# 2_Shutdown.net
KiCad netlist of a schematic drawn in Altium Designer
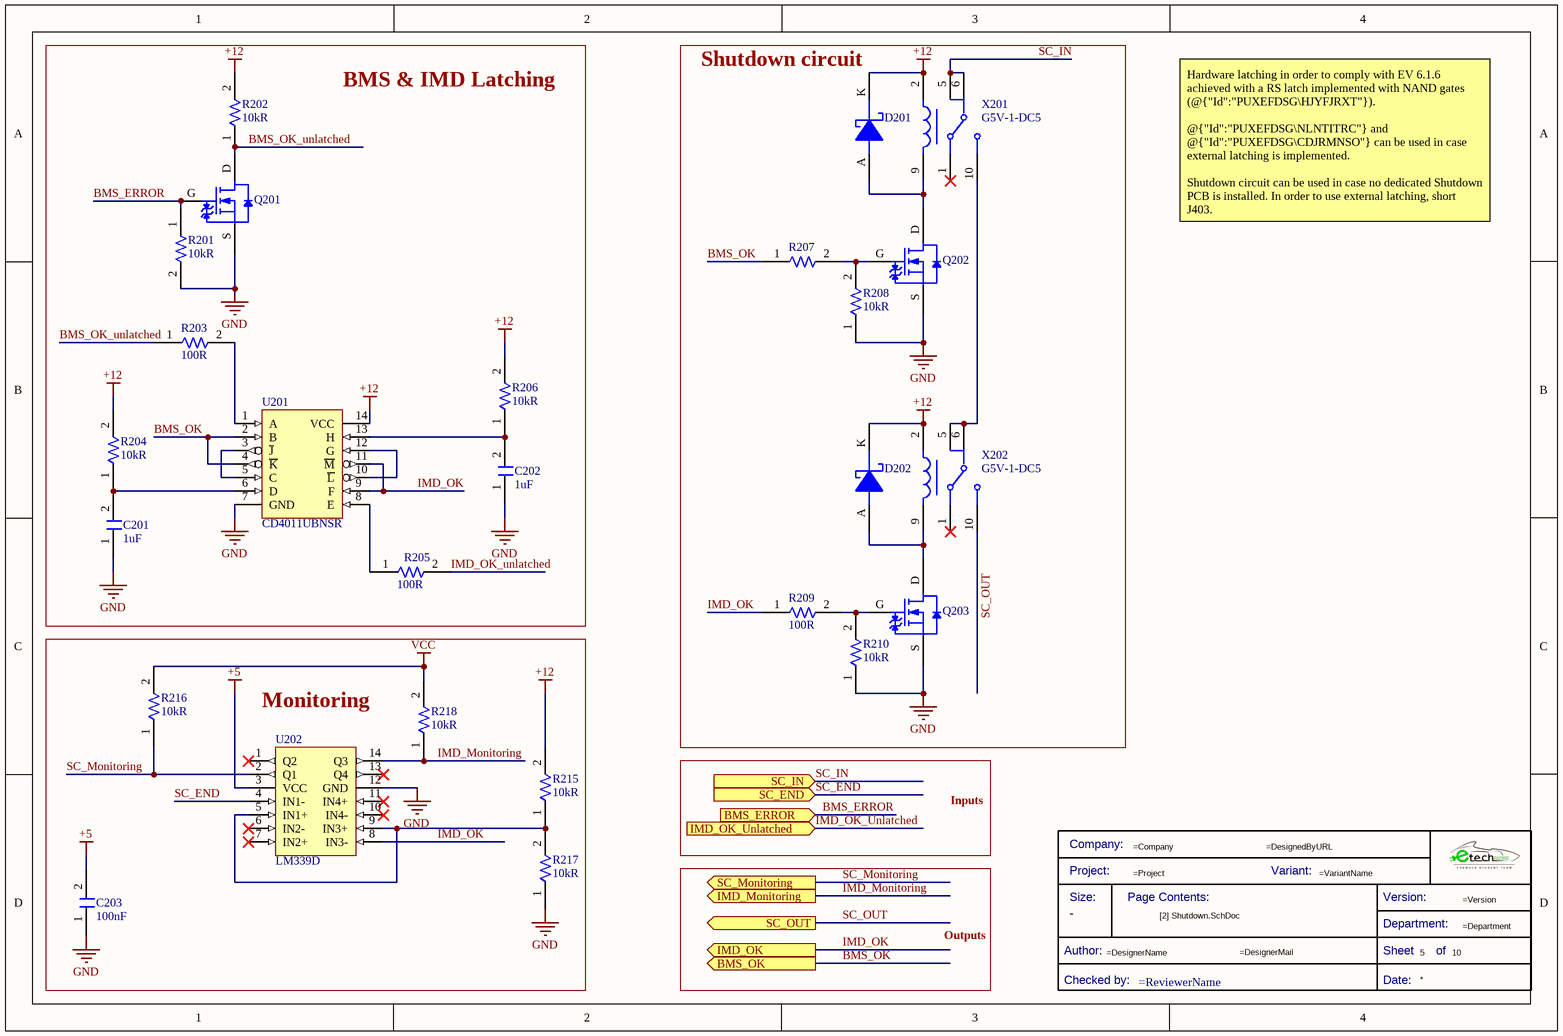
[diagram p0: [2] Shutdown.SchDoc]

(export (version "E")
  (design (tool "Eeschema 10.0.6"))
  (components
    (comp (ref "*")
      (value "Title Block_template")
      (description "Standard Title Block")
      (fields (field (name "SIZE") "-"))
      (libsource (lib "e-Tech_Racing") (part "Title Block_template"))
    )
    (comp (ref "C201")
      (value "885012207103")
      (footprint "C0805FNPC-R")
      (fields
        (field (name "TOLERANCE") "10%")
        (field (name "CAPACITANCE") "1uF")
        (field (name ".CREATOR") "GP")
      )
      (libsource (lib "Passives") (part "C1u-50V-0805FNPC-X7R"))
    )
    (comp (ref "C202")
      (value "885012207103")
      (footprint "C0805FNPC-R")
      (fields
        (field (name "TOLERANCE") "10%")
        (field (name "CAPACITANCE") "1uF")
        (field (name ".CREATOR") "GP")
      )
      (libsource (lib "Passives") (part "C1u-50V-0805FNPC-X7R"))
    )
    (comp (ref "C203")
      (value "885012207098")
      (footprint "C0805FNPC-R")
      (description "Cap, 0.1ΜF, 50V, 10%, X7R, 0805")
      (fields
        (field (name "TOLERANCE") "10%")
        (field (name "CAPACITANCE") "100nF")
        (field (name ".CREATOR") "DR")
      )
      (libsource (lib "Passives") (part "C100n-50V-0805FNPC-X7R"))
    )
    (comp (ref "D201")
      (value "MBR0530")
      (footprint "DSC-SOD123")
      (description "VR=30V IF=500mA 30pF P=410mW")
      (fields (field (name ".CREATOR") "GP"))
      (libsource (lib "Filter components") (part "DSC-0.5/30-SOD123"))
    )
    (comp (ref "D202")
      (value "MBR0530")
      (footprint "DSC-SOD123")
      (description "VR=30V IF=500mA 30pF P=410mW")
      (fields (field (name ".CREATOR") "GP"))
      (libsource (lib "Filter components") (part "DSC-0.5/30-SOD123"))
    )
    (comp (ref "Q201")
      (value "CPH3455-TL-H")
      (footprint "TRT-NCH-3/35-CPH")
      (description "CPH3455-TL-H N-channel MOSFET Transistor; 3 A; 35 V; 3-Pin CPH")
      (fields (field (name "MANUFACTURER") "ON Semiconductor") (field (name ".CREATOR") "GP"))
      (libsource (lib "Semiconductor") (part "TRT-NCH-3/35-CPH"))
    )
    (comp (ref "Q202")
      (value "CPH3455-TL-H")
      (footprint "TRT-NCH-3/35-CPH")
      (description "CPH3455-TL-H N-channel MOSFET Transistor; 3 A; 35 V; 3-Pin CPH")
      (fields (field (name "MANUFACTURER") "ON Semiconductor") (field (name ".CREATOR") "GP"))
      (libsource (lib "Semiconductor") (part "TRT-NCH-3/35-CPH"))
    )
    (comp (ref "Q203")
      (value "CPH3455-TL-H")
      (footprint "TRT-NCH-3/35-CPH")
      (description "CPH3455-TL-H N-channel MOSFET Transistor; 3 A; 35 V; 3-Pin CPH")
      (fields (field (name "MANUFACTURER") "ON Semiconductor") (field (name ".CREATOR") "GP"))
      (libsource (lib "Semiconductor") (part "TRT-NCH-3/35-CPH"))
    )
    (comp (ref "R201")
      (value "CR0805-JW-103ELF")
      (footprint "R0805FTK")
      (fields
        (field (name "TOLERANCE") "5%")
        (field (name "RESISTANCE") "10kR")
        (field (name ".CREATOR") "DR")
      )
      (libsource (lib "Passives") (part "R10k-0805FTK"))
    )
    (comp (ref "R202")
      (value "CR0805-JW-103ELF")
      (footprint "R0805FTK")
      (fields
        (field (name "TOLERANCE") "5%")
        (field (name "RESISTANCE") "10kR")
        (field (name ".CREATOR") "DR")
      )
      (libsource (lib "Passives") (part "R10k-0805FTK"))
    )
    (comp (ref "R203")
      (value "CR0805-FX-1000ELF")
      (footprint "R0805FTK")
      (description "Res Thick Film 0805 100 Ohm 1% 1/8W ±100ppm/°C Molded SMD SMD Paper Tape on Plastic Reel")
      (fields
        (field (name "TOLERANCE") "1%")
        (field (name "RESISTANCE") "100R")
        (field (name ".CREATOR") "DR")
      )
      (libsource (lib "Passives") (part "R100-0805FTK"))
    )
    (comp (ref "R204")
      (value "CR0805-JW-103ELF")
      (footprint "R0805FTK")
      (fields
        (field (name "TOLERANCE") "5%")
        (field (name "RESISTANCE") "10kR")
        (field (name ".CREATOR") "DR")
      )
      (libsource (lib "Passives") (part "R10k-0805FTK"))
    )
    (comp (ref "R205")
      (value "CR0805-FX-1000ELF")
      (footprint "R0805FTK")
      (description "Res Thick Film 0805 100 Ohm 1% 1/8W ±100ppm/°C Molded SMD SMD Paper Tape on Plastic Reel")
      (fields
        (field (name "TOLERANCE") "1%")
        (field (name "RESISTANCE") "100R")
        (field (name ".CREATOR") "DR")
      )
      (libsource (lib "Passives") (part "R100-0805FTK"))
    )
    (comp (ref "R206")
      (value "CR0805-JW-103ELF")
      (footprint "R0805FTK")
      (fields
        (field (name "TOLERANCE") "5%")
        (field (name "RESISTANCE") "10kR")
        (field (name ".CREATOR") "DR")
      )
      (libsource (lib "Passives") (part "R10k-0805FTK"))
    )
    (comp (ref "R207")
      (value "CR0805-FX-1000ELF")
      (footprint "R0805FTK")
      (description "Res Thick Film 0805 100 Ohm 1% 1/8W ±100ppm/°C Molded SMD SMD Paper Tape on Plastic Reel")
      (fields (field (name "TOLERANCE") "1%") (field (name ".CREATOR") "DR"))
      (libsource (lib "Passives") (part "R100-0805FTK"))
    )
    (comp (ref "R208")
      (value "CR0805-JW-103ELF")
      (footprint "R0805FTK")
      (fields
        (field (name "TOLERANCE") "5%")
        (field (name "RESISTANCE") "10kR")
        (field (name ".CREATOR") "DR")
      )
      (libsource (lib "Passives") (part "R10k-0805FTK"))
    )
    (comp (ref "R209")
      (value "CR0805-FX-1000ELF")
      (footprint "R0805FTK")
      (description "Res Thick Film 0805 100 Ohm 1% 1/8W ±100ppm/°C Molded SMD SMD Paper Tape on Plastic Reel")
      (fields
        (field (name "TOLERANCE") "1%")
        (field (name "RESISTANCE") "100R")
        (field (name ".CREATOR") "DR")
      )
      (libsource (lib "Passives") (part "R100-0805FTK"))
    )
    (comp (ref "R210")
      (value "CR0805-JW-103ELF")
      (footprint "R0805FTK")
      (fields
        (field (name "TOLERANCE") "5%")
        (field (name "RESISTANCE") "10kR")
        (field (name ".CREATOR") "DR")
      )
      (libsource (lib "Passives") (part "R10k-0805FTK"))
    )
    (comp (ref "R215")
      (value "CR0805-JW-103ELF")
      (footprint "R0805FTK")
      (fields
        (field (name "TOLERANCE") "5%")
        (field (name "RESISTANCE") "10kR")
        (field (name ".CREATOR") "DR")
      )
      (libsource (lib "Passives") (part "R10k-0805FTK"))
    )
    (comp (ref "R216")
      (value "CR0805-JW-103ELF")
      (footprint "R0805FTK")
      (fields
        (field (name "TOLERANCE") "5%")
        (field (name "RESISTANCE") "10kR")
        (field (name ".CREATOR") "DR")
      )
      (libsource (lib "Passives") (part "R10k-0805FTK"))
    )
    (comp (ref "R217")
      (value "CR0805-JW-103ELF")
      (footprint "R0805FTK")
      (fields
        (field (name "TOLERANCE") "5%")
        (field (name "RESISTANCE") "10kR")
        (field (name ".CREATOR") "DR")
      )
      (libsource (lib "Passives") (part "R10k-0805FTK"))
    )
    (comp (ref "R218")
      (value "CR0805-JW-103ELF")
      (footprint "R0805FTK")
      (fields
        (field (name "TOLERANCE") "5%")
        (field (name "RESISTANCE") "10kR")
        (field (name ".CREATOR") "DR")
      )
      (libsource (lib "Passives") (part "R10k-0805FTK"))
    )
    (comp (ref "U201")
      (value "CD4011UBSNR")
      (footprint "ARRAY_4_NAND")
      (description "CD4011UB Cmos Quad 2-INPUT Nand")
      (fields
        (field (name "MANUFACTURER") "Texas Instruments")
        (field (name "MANUFACTURER PART NUMBER") "CD4011UBNSR")
        (field (name ".CREATOR") "DO")
      )
      (libsource (lib "Integrated circuits") (part "Array_4_NAND"))
    )
    (comp (ref "U202")
      (value "LM339D")
      (footprint "Array_4_Amp_LM339D")
      (description "Comparator Quad ±18V/36V 14-Pin SOIC Tube")
      (fields
        (field (name "MANUFACTURER") "Texas Instruments")
        (field (name "MANUFACTURER PART NUMBER") "LM339D")
        (field (name ".CREATOR") "DO")
      )
      (libsource (lib "Integrated circuits") (part "Array_4_Amp_LM339D"))
    )
    (comp (ref "X201")
      (value "G5V-1-DC5")
      (footprint "Relay_G5V-1-DC5")
      (description "Electromechanical Relay SPDT 1A 5VDC 167Ohm Through Hole")
      (fields
        (field (name "MANUFACTURER") "Omron")
        (field (name "SUPPLIER PART NUMBER 1") "G5V-1-DC5")
        (field (name ".CREATOR") "DO")
      )
      (libsource (lib "Electromechanical") (part "Relay_G5V-1-DC5"))
    )
    (comp (ref "X202")
      (value "G5V-1-DC5")
      (footprint "Relay_G5V-1-DC5")
      (description "Electromechanical Relay SPDT 1A 5VDC 167Ohm Through Hole")
      (fields
        (field (name "MANUFACTURER") "Omron")
        (field (name "SUPPLIER PART NUMBER 1") "G5V-1-DC5")
        (field (name ".CREATOR") "DO")
      )
      (libsource (lib "Electromechanical") (part "Relay_G5V-1-DC5"))
    )
  )
  (nets
    (net (code "1") (name "+5") (class "Default")
      (node (ref "C203") (pin "2") (pinfunction "2_2") (pintype "passive"))
      (node (ref "U202") (pin "3") (pinfunction "VCC_3") (pintype "power_in"))
    )
    (net (code "2") (name "+12") (class "Default")
      (node (ref "D201") (pin "K") (pinfunction "K_K") (pintype "passive"))
      (node (ref "D202") (pin "K") (pinfunction "K_K") (pintype "passive"))
      (node (ref "R202") (pin "2") (pinfunction "2_2") (pintype "passive"))
      (node (ref "R204") (pin "2") (pinfunction "2_2") (pintype "passive"))
      (node (ref "R206") (pin "2") (pinfunction "2_2") (pintype "passive"))
      (node (ref "R215") (pin "2") (pinfunction "2_2") (pintype "passive"))
      (node (ref "U201") (pin "14") (pinfunction "VCC_14") (pintype "power_in"))
      (node (ref "X201") (pin "2") (pinfunction "2_2") (pintype "passive"))
      (node (ref "X202") (pin "2") (pinfunction "2_2") (pintype "passive"))
    )
    (net (code "3") (name "/BMS_ERROR") (class "Default")
      (node (ref "Q201") (pin "G") (pinfunction "G_G") (pintype "passive"))
      (node (ref "R201") (pin "1") (pinfunction "1_1") (pintype "passive"))
    )
    (net (code "4") (name "/BMS_OK") (class "Default")
      (node (ref "R207") (pin "1") (pinfunction "1_1") (pintype "passive"))
      (node (ref "U201") (pin "2") (pinfunction "B_2") (pintype "input"))
      (node (ref "U201") (pin "4") (pinfunction "~{K}_4") (pintype "output"))
    )
    (net (code "5") (name "/BMS_OK_unlatched") (class "Default")
      (node (ref "Q201") (pin "D") (pinfunction "D_D") (pintype "passive"))
      (node (ref "R202") (pin "1") (pinfunction "1_1") (pintype "passive"))
      (node (ref "R203") (pin "1") (pinfunction "1_1") (pintype "passive"))
    )
    (net (code "6") (name "/IMD_Monitoring") (class "Default")
      (node (ref "R218") (pin "1") (pinfunction "1_1") (pintype "passive"))
      (node (ref "U202") (pin "14") (pinfunction "Q3_14") (pintype "output"))
    )
    (net (code "7") (name "/IMD_OK") (class "Default")
      (node (ref "R209") (pin "1") (pinfunction "1_1") (pintype "passive"))
      (node (ref "U201") (pin "11") (pinfunction "~{M}_11") (pintype "output"))
      (node (ref "U201") (pin "9") (pinfunction "F_9") (pintype "input"))
      (node (ref "U202") (pin "8") (pinfunction "IN3-_8") (pintype "input"))
    )
    (net (code "9") (name "/IMD_OK_unlatched") (class "Default")
      (node (ref "R205") (pin "2") (pinfunction "2_2") (pintype "passive"))
    )
    (net (code "10") (name "/SC_END") (class "Default")
      (node (ref "U202") (pin "4") (pinfunction "IN1-_4") (pintype "input"))
    )
    (net (code "11") (name "/SC_IN") (class "Default")
      (node (ref "X201") (pin "5") (pinfunction "5_5") (pintype "passive"))
      (node (ref "X201") (pin "6") (pinfunction "6_6") (pintype "passive"))
    )
    (net (code "12") (name "/SC_Monitoring") (class "Default")
      (node (ref "R216") (pin "1") (pinfunction "1_1") (pintype "passive"))
      (node (ref "U202") (pin "2") (pinfunction "Q1_2") (pintype "output"))
    )
    (net (code "13") (name "/SC_OUT") (class "Default")
      (node (ref "X202") (pin "10") (pinfunction "10_10") (pintype "passive"))
    )
    (net (code "14") (name "GND") (class "Default")
      (node (ref "C201") (pin "1") (pinfunction "1_1") (pintype "passive"))
      (node (ref "C202") (pin "1") (pinfunction "1_1") (pintype "passive"))
      (node (ref "C203") (pin "1") (pinfunction "1_1") (pintype "passive"))
      (node (ref "Q201") (pin "S") (pinfunction "S_S") (pintype "passive"))
      (node (ref "Q202") (pin "S") (pinfunction "S_S") (pintype "passive"))
      (node (ref "Q203") (pin "S") (pinfunction "S_S") (pintype "passive"))
      (node (ref "R201") (pin "2") (pinfunction "2_2") (pintype "passive"))
      (node (ref "R208") (pin "1") (pinfunction "1_1") (pintype "passive"))
      (node (ref "R210") (pin "1") (pinfunction "1_1") (pintype "passive"))
      (node (ref "R217") (pin "1") (pinfunction "1_1") (pintype "passive"))
      (node (ref "U201") (pin "7") (pinfunction "GND_7") (pintype "power_in"))
      (node (ref "U202") (pin "12") (pinfunction "GND_12") (pintype "power_in"))
    )
    (net (code "15") (name "Net-(D201-PadA)") (class "Default")
      (node (ref "D201") (pin "A") (pinfunction "A_A") (pintype "passive"))
      (node (ref "Q202") (pin "D") (pinfunction "D_D") (pintype "passive"))
      (node (ref "X201") (pin "9") (pinfunction "9_9") (pintype "passive"))
    )
    (net (code "16") (name "Net-(D202-PadA)") (class "Default")
      (node (ref "D202") (pin "A") (pinfunction "A_A") (pintype "passive"))
      (node (ref "Q203") (pin "D") (pinfunction "D_D") (pintype "passive"))
      (node (ref "X202") (pin "9") (pinfunction "9_9") (pintype "passive"))
    )
    (net (code "17") (name "Net-(Q202-PadG)") (class "Default")
      (node (ref "Q202") (pin "G") (pinfunction "G_G") (pintype "passive"))
      (node (ref "R207") (pin "2") (pinfunction "2_2") (pintype "passive"))
      (node (ref "R208") (pin "2") (pinfunction "2_2") (pintype "passive"))
    )
    (net (code "18") (name "Net-(Q203-PadG)") (class "Default")
      (node (ref "Q203") (pin "G") (pinfunction "G_G") (pintype "passive"))
      (node (ref "R209") (pin "2") (pinfunction "2_2") (pintype "passive"))
      (node (ref "R210") (pin "2") (pinfunction "2_2") (pintype "passive"))
    )
    (net (code "19") (name "Net-(U201-A)") (class "Default")
      (node (ref "R203") (pin "2") (pinfunction "2_2") (pintype "passive"))
      (node (ref "U201") (pin "1") (pinfunction "A_1") (pintype "input"))
    )
    (net (code "20") (name "Net-(U201-C)") (class "Default")
      (node (ref "U201") (pin "3") (pinfunction "~{J}_3") (pintype "output"))
      (node (ref "U201") (pin "5") (pinfunction "C_5") (pintype "input"))
    )
    (net (code "21") (name "Net-(U201-D)") (class "Default")
      (node (ref "C201") (pin "2") (pinfunction "2_2") (pintype "passive"))
      (node (ref "R204") (pin "1") (pinfunction "1_1") (pintype "passive"))
      (node (ref "U201") (pin "6") (pinfunction "D_6") (pintype "input"))
    )
    (net (code "22") (name "Net-(U201-E)") (class "Default")
      (node (ref "R205") (pin "1") (pinfunction "1_1") (pintype "passive"))
      (node (ref "U201") (pin "8") (pinfunction "E_8") (pintype "input"))
    )
    (net (code "23") (name "Net-(U201-G)") (class "Default")
      (node (ref "U201") (pin "10") (pinfunction "~{L}_10") (pintype "output"))
      (node (ref "U201") (pin "12") (pinfunction "G_12") (pintype "input"))
    )
    (net (code "24") (name "Net-(U201-H)") (class "Default")
      (node (ref "C202") (pin "2") (pinfunction "2_2") (pintype "passive"))
      (node (ref "R206") (pin "1") (pinfunction "1_1") (pintype "passive"))
      (node (ref "U201") (pin "13") (pinfunction "H_13") (pintype "input"))
    )
    (net (code "25") (name "Net-(U202-IN1+)") (class "Default")
      (node (ref "R215") (pin "1") (pinfunction "1_1") (pintype "passive"))
      (node (ref "R217") (pin "2") (pinfunction "2_2") (pintype "passive"))
      (node (ref "U202") (pin "5") (pinfunction "IN1+_5") (pintype "input"))
      (node (ref "U202") (pin "9") (pinfunction "IN3+_9") (pintype "input"))
    )
    (net (code "26") (name "Net-(X201-Pad10)") (class "Default")
      (node (ref "X201") (pin "10") (pinfunction "10_10") (pintype "passive"))
      (node (ref "X202") (pin "5") (pinfunction "5_5") (pintype "passive"))
      (node (ref "X202") (pin "6") (pinfunction "6_6") (pintype "passive"))
    )
    (net (code "27") (name "VCC") (class "Default")
      (node (ref "R216") (pin "2") (pinfunction "2_2") (pintype "passive"))
      (node (ref "R218") (pin "2") (pinfunction "2_2") (pintype "passive"))
    )
    (net (code "28") (name "unconnected-(U202-IN2+-Pad7)") (class "Default")
      (node (ref "U202") (pin "7") (pinfunction "IN2+_7") (pintype "input+no_connect"))
    )
    (net (code "29") (name "unconnected-(U202-IN2--Pad6)") (class "Default")
      (node (ref "U202") (pin "6") (pinfunction "IN2-_6") (pintype "input+no_connect"))
    )
    (net (code "30") (name "unconnected-(U202-IN4+-Pad11)") (class "Default")
      (node (ref "U202") (pin "11") (pinfunction "IN4+_11") (pintype "input+no_connect"))
    )
    (net (code "31") (name "unconnected-(U202-IN4--Pad10)") (class "Default")
      (node (ref "U202") (pin "10") (pinfunction "IN4-_10") (pintype "input+no_connect"))
    )
    (net (code "32") (name "unconnected-(U202-Q2-Pad1)") (class "Default")
      (node (ref "U202") (pin "1") (pinfunction "Q2_1") (pintype "output+no_connect"))
    )
    (net (code "33") (name "unconnected-(U202-Q4-Pad13)") (class "Default")
      (node (ref "U202") (pin "13") (pinfunction "Q4_13") (pintype "output+no_connect"))
    )
    (net (code "34") (name "unconnected-(X201-Pad1)") (class "Default")
      (node (ref "X201") (pin "1") (pinfunction "1_1") (pintype "passive+no_connect"))
    )
    (net (code "35") (name "unconnected-(X202-Pad1)") (class "Default")
      (node (ref "X202") (pin "1") (pinfunction "1_1") (pintype "passive+no_connect"))
    )
  )
)
